# Power.net
KiCad netlist of a schematic drawn in Altium Designer
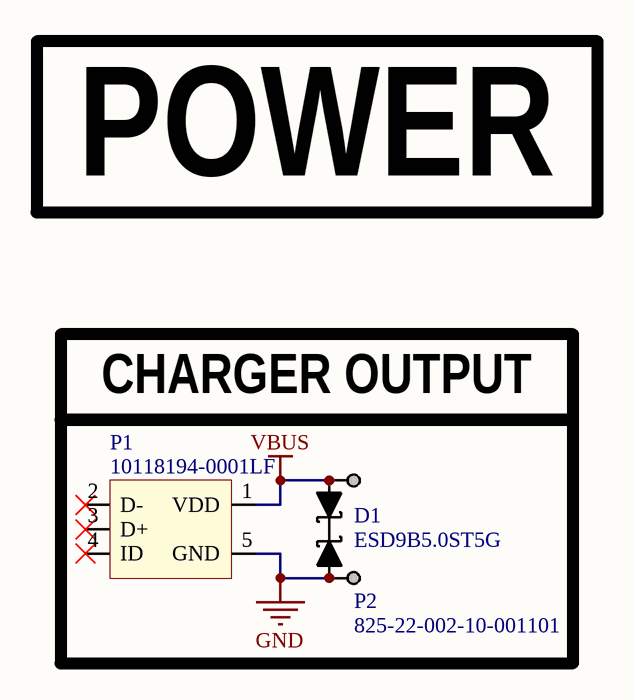
[diagram p0: Power.SchDoc]

(export (version "E")
  (design (tool "Eeschema 10.0.6"))
  (components
    (comp (ref "D1")
      (value "ESD9B5.0ST5G")
      (footprint "ESD9B5.0ST5G")
      (description "TVS DIODE 5V SOD923")
      (libsource (lib "smLib") (part "ESD9B5.0ST5G"))
    )
    (comp (ref "P1")
      (value "10118194-0001LF")
      (footprint "10118194-0001LF")
      (libsource (lib "smLib") (part "10118194-0001LF"))
    )
    (comp (ref "P2")
      (value "825-22-002-10-001101")
      (footprint "825-22-002-10-001101")
      (description "2 Position Spring Piston Connector Through Hole")
      (libsource (lib "smLib") (part "825-22-002-10-001101"))
    )
  )
  (nets
    (net (code "1") (name "GND") (class "Default")
      (node (ref "D1") (pin "1") (pinfunction "1_1") (pintype "passive"))
      (node (ref "P1") (pin "5") (pinfunction "GND_5") (pintype "passive"))
      (node (ref "P2") (pin "2") (pinfunction "2_2") (pintype "passive"))
    )
    (net (code "2") (name "VBUS") (class "Default")
      (node (ref "D1") (pin "2") (pinfunction "2_2") (pintype "passive"))
      (node (ref "P1") (pin "1") (pinfunction "VDD_1") (pintype "passive"))
      (node (ref "P2") (pin "1") (pinfunction "1_1") (pintype "passive"))
    )
    (net (code "3") (name "unconnected-(P1-D+-Pad3)") (class "Default")
      (node (ref "P1") (pin "3") (pinfunction "D+_3") (pintype "passive+no_connect"))
    )
    (net (code "4") (name "unconnected-(P1-D--Pad2)") (class "Default")
      (node (ref "P1") (pin "2") (pinfunction "D-_2") (pintype "passive+no_connect"))
    )
    (net (code "5") (name "unconnected-(P1-ID-Pad4)") (class "Default")
      (node (ref "P1") (pin "4") (pinfunction "ID_4") (pintype "passive+no_connect"))
    )
  )
)
